# elrs_TX_E28.net
KiCad netlist of a schematic drawn in EasyEDA
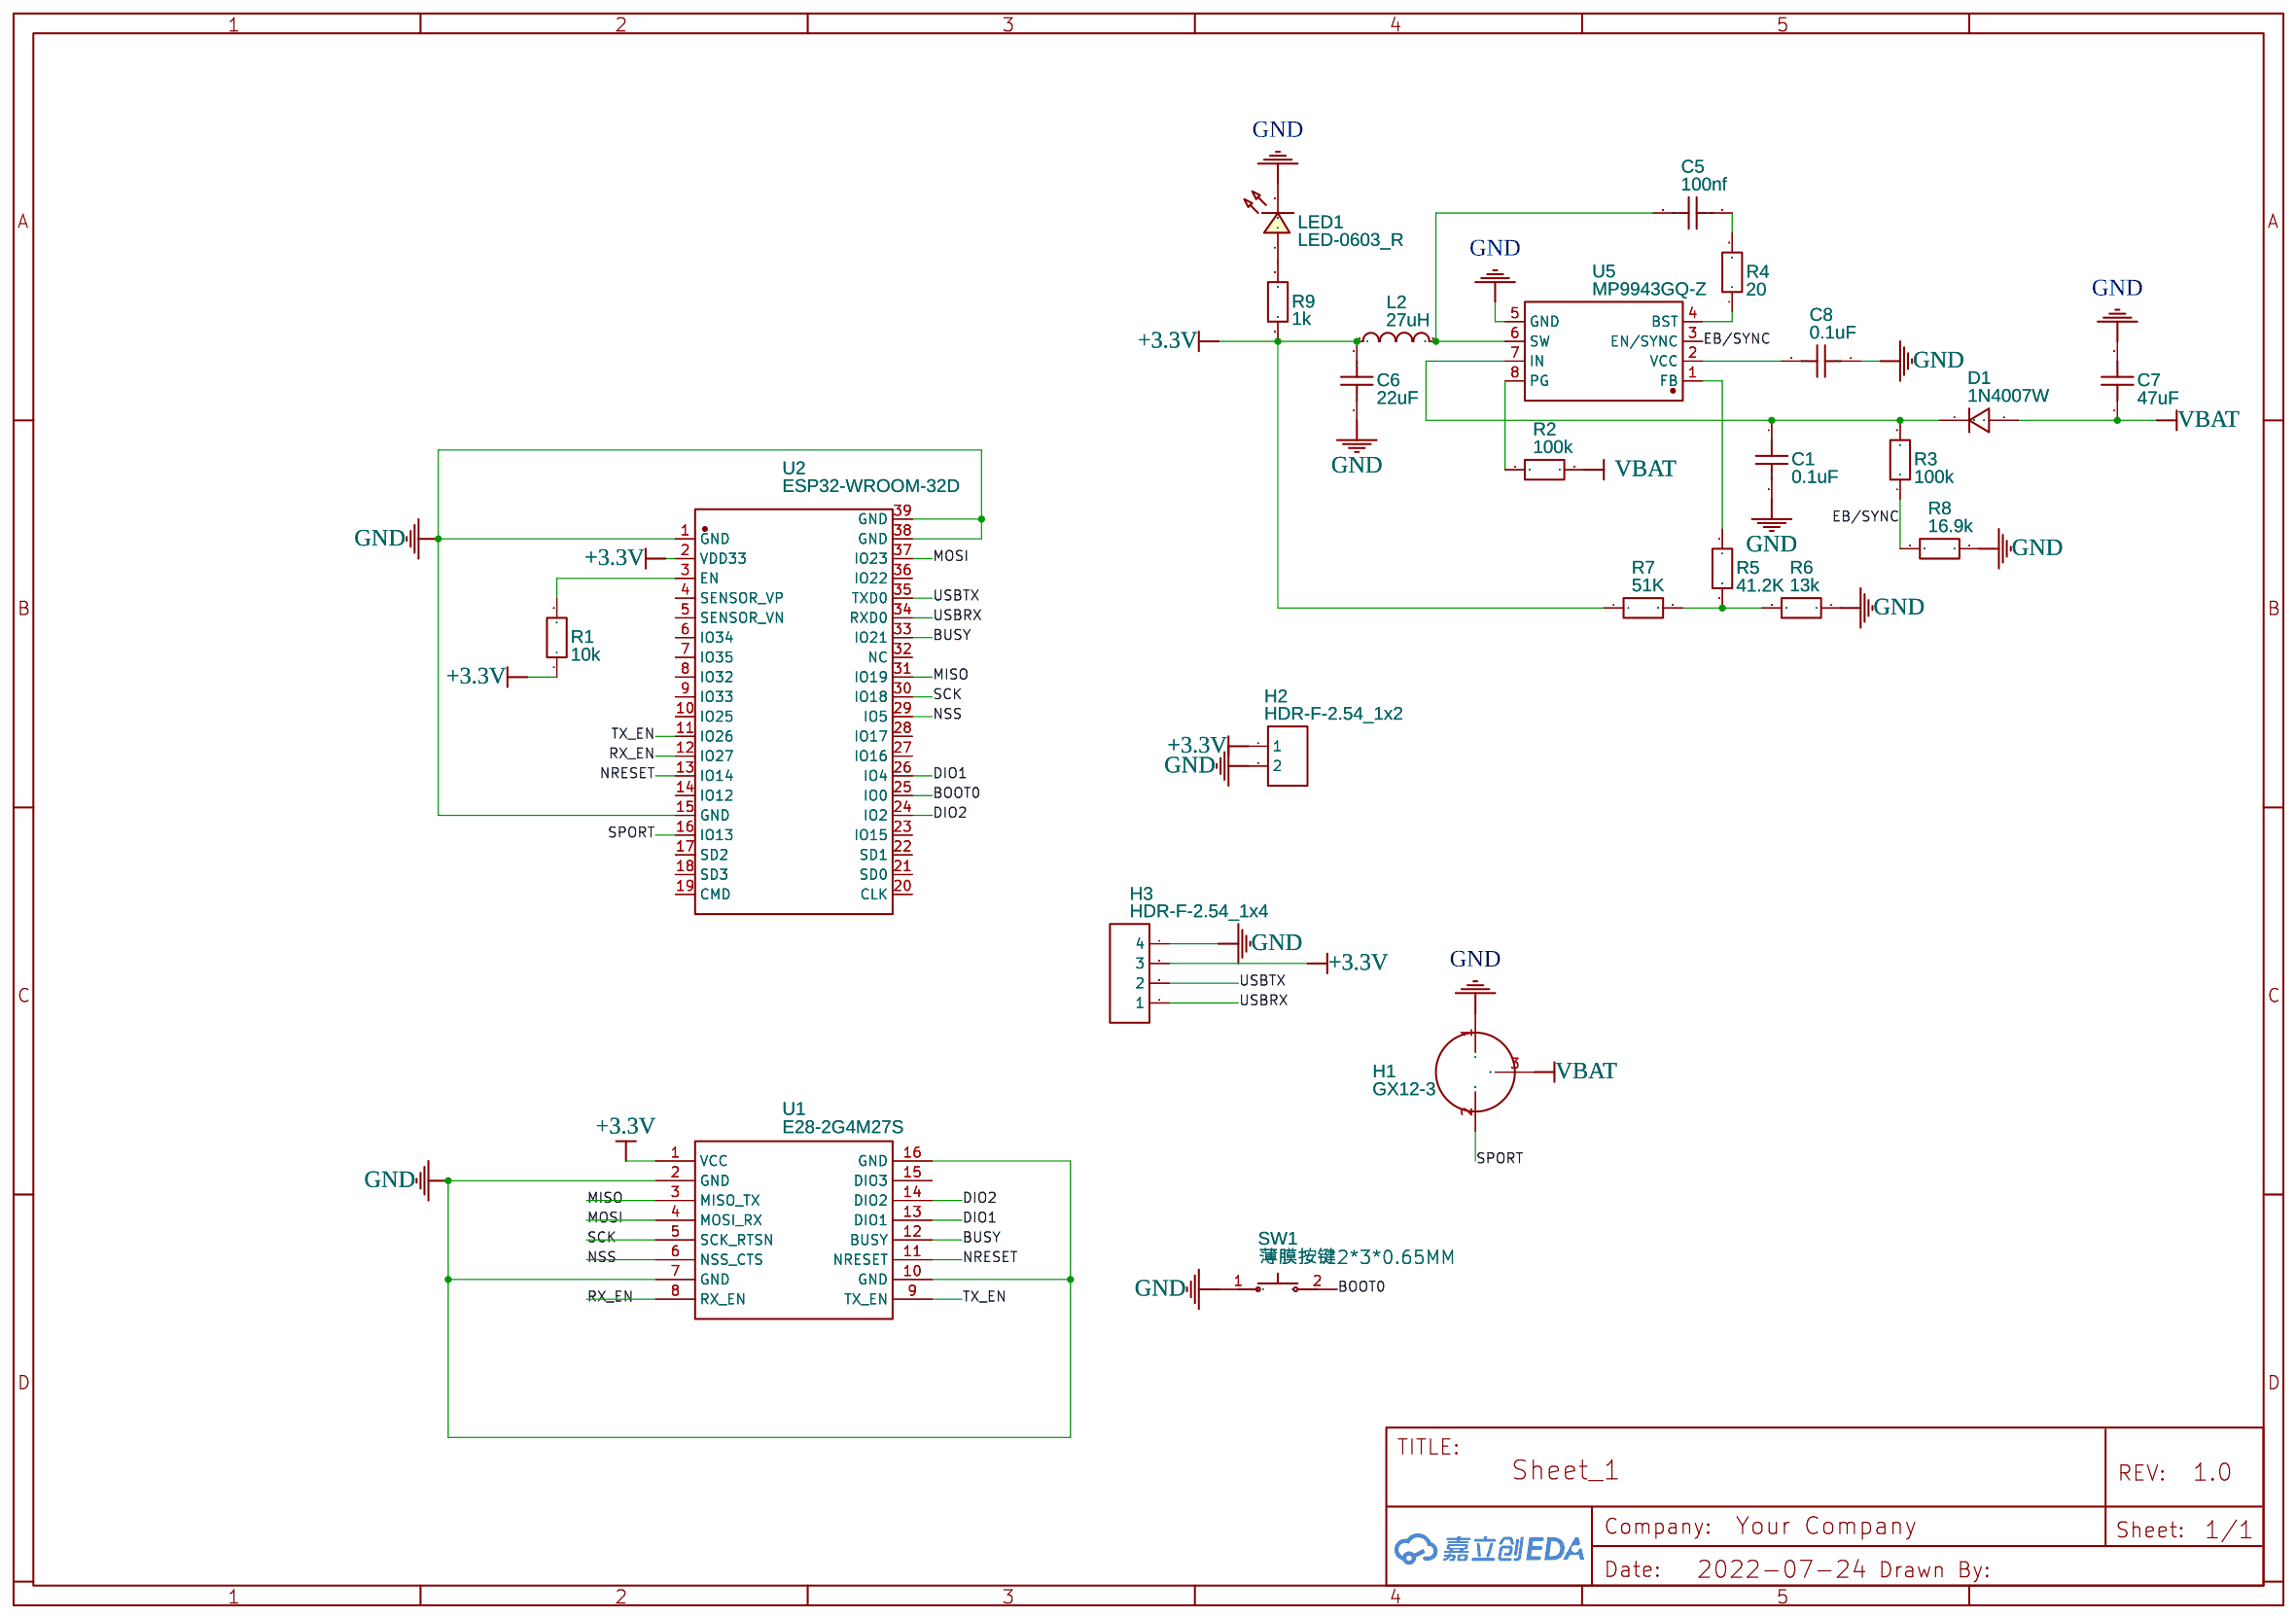
[diagram p0: schematic sheet]

(export (version "E")
  (design (tool "Eeschema 10.0.6"))
  (components
    (comp (ref "C1") (value "0.1uF") (libsource (lib "") (part "C_0603_US_1")))
    (comp (ref "C5") (value "100nf") (libsource (lib "") (part "C_0603_US")))
    (comp (ref "C6") (value "22uF") (libsource (lib "") (part "C_0603_US_2")))
    (comp (ref "C7") (value "47uF") (libsource (lib "") (part "C_0603_US_2")))
    (comp (ref "C8") (value "0.1uF") (libsource (lib "") (part "C_0603_US")))
    (comp (ref "D1")
      (value "1N4007W")
      (fields (field (name "BOM_Supplier Part") "C328592"))
      (libsource (lib "") (part "1N4007W"))
    )
    (comp (ref "H1") (value "GX12-3") (libsource (lib "") (part "GX12-3")))
    (comp (ref "H2")
      (value "HDR-F-2.54_1x2")
      (fields (field (name "BOM_Supplier Part") "C49661"))
      (libsource (lib "") (part "HDR-F-2.54_1x2"))
    )
    (comp (ref "H3")
      (value "HDR-F-2.54_1x4")
      (fields (field (name "BOM_Supplier Part") "C225501"))
      (libsource (lib "") (part "HDR-F-2.54_1x4"))
    )
    (comp (ref "L2") (value "27uH") (libsource (lib "") (part "L0603_US")))
    (comp (ref "LED1")
      (value "LED-0603_R")
      (fields
        (field (name "BOM_Manufacturer Part") "19-217/R6C-AL1M2VY/3T")
        (field (name "BOM_Supplier Part") "C72044")
      )
      (libsource (lib "") (part "LED-0603_R"))
    )
    (comp (ref "R1") (value "10k") (libsource (lib "") (part "R_0603_EU_2")))
    (comp (ref "R2") (value "100k") (libsource (lib "") (part "R_0603_EU")))
    (comp (ref "R3") (value "100k") (libsource (lib "") (part "R_0603_EU_2")))
    (comp (ref "R4") (value "20") (libsource (lib "") (part "R_0603_EU_2")))
    (comp (ref "R5") (value "41.2K") (libsource (lib "") (part "R_0603_EU_1")))
    (comp (ref "R6") (value "13k") (libsource (lib "") (part "R_0603_EU_3")))
    (comp (ref "R7") (value "51K") (libsource (lib "") (part "R_0603_EU")))
    (comp (ref "R8") (value "16.9k") (libsource (lib "") (part "R_0603_EU_3")))
    (comp (ref "R9") (value "1k") (libsource (lib "") (part "R_0603_EU_2")))
    (comp (ref "SW1")
      (value "薄膜按键2*3*0.65MM")
      (fields (field (name "BOM_Supplier Part") "C9900015708"))
      (libsource (lib "") (part "薄膜按键2*3*0.65MM"))
    )
    (comp (ref "U1")
      (value "E28-2G4M27S")
      (fields (field (name "BOM_Supplier Part") "C411312"))
      (libsource (lib "") (part "E28-2G4M27S"))
    )
    (comp (ref "U2")
      (value "ESP32-WROOM-32D")
      (fields (field (name "BOM_Supplier Part") "C473012"))
      (libsource (lib "") (part "ESP32-WROOM-32D"))
    )
    (comp (ref "U5")
      (value "MP9943GQ-Z")
      (fields (field (name "BOM_Supplier Part") "C477821"))
      (libsource (lib "") (part "MP9943GQ-Z"))
    )
  )
  (nets
    (net (code "1") (name "+3.3V") (class "Default")
      (node (ref "C6") (pin "2") (pinfunction "2_2") (pintype "unspecified"))
      (node (ref "H2") (pin "1") (pinfunction "1_1") (pintype "input"))
      (node (ref "H3") (pin "3") (pinfunction "3_3") (pintype "unspecified"))
      (node (ref "L2") (pin "1") (pinfunction "1_1") (pintype "unspecified"))
      (node (ref "R1") (pin "1") (pinfunction "1_1") (pintype "unspecified"))
      (node (ref "R7") (pin "1") (pinfunction "1_1") (pintype "unspecified"))
      (node (ref "R9") (pin "1") (pinfunction "1_1") (pintype "unspecified"))
      (node (ref "U1") (pin "1") (pinfunction "VCC_1") (pintype "unspecified"))
      (node (ref "U2") (pin "2") (pinfunction "VDD33_2") (pintype "unspecified"))
    )
    (net (code "2") (name "/BOOT0") (class "Default")
      (node (ref "SW1") (pin "2") (pinfunction "2_2") (pintype "unspecified"))
      (node (ref "U2") (pin "25") (pinfunction "IO0_25") (pintype "unspecified"))
    )
    (net (code "3") (name "/BUSY") (class "Default")
      (node (ref "U1") (pin "12") (pinfunction "BUSY_12") (pintype "unspecified"))
      (node (ref "U2") (pin "33") (pinfunction "IO21_33") (pintype "unspecified"))
    )
    (net (code "4") (name "/DIO1") (class "Default")
      (node (ref "U1") (pin "13") (pinfunction "DIO1_13") (pintype "unspecified"))
      (node (ref "U2") (pin "26") (pinfunction "IO4_26") (pintype "unspecified"))
    )
    (net (code "5") (name "/DIO2") (class "Default")
      (node (ref "U1") (pin "14") (pinfunction "DIO2_14") (pintype "unspecified"))
      (node (ref "U2") (pin "24") (pinfunction "IO2_24") (pintype "unspecified"))
    )
    (net (code "6") (name "/EB{slash}SYNC") (class "Default")
      (node (ref "R3") (pin "1") (pinfunction "1_1") (pintype "unspecified"))
      (node (ref "R8") (pin "2") (pinfunction "2_2") (pintype "unspecified"))
      (node (ref "U5") (pin "3") (pinfunction "EN/SYNC_3") (pintype "unspecified"))
    )
    (net (code "7") (name "/MISO") (class "Default")
      (node (ref "U1") (pin "3") (pinfunction "MISO_TX_3") (pintype "unspecified"))
      (node (ref "U2") (pin "31") (pinfunction "IO19_31") (pintype "unspecified"))
    )
    (net (code "8") (name "/MOSI") (class "Default")
      (node (ref "U1") (pin "4") (pinfunction "MOSI_RX_4") (pintype "unspecified"))
      (node (ref "U2") (pin "37") (pinfunction "IO23_37") (pintype "unspecified"))
    )
    (net (code "9") (name "/NRESET") (class "Default")
      (node (ref "U1") (pin "11") (pinfunction "NRESET_11") (pintype "unspecified"))
      (node (ref "U2") (pin "13") (pinfunction "IO14_13") (pintype "unspecified"))
    )
    (net (code "10") (name "/NSS") (class "Default")
      (node (ref "U1") (pin "6") (pinfunction "NSS_CTS_6") (pintype "unspecified"))
      (node (ref "U2") (pin "29") (pinfunction "IO5_29") (pintype "unspecified"))
    )
    (net (code "11") (name "/RX_EN") (class "Default")
      (node (ref "U1") (pin "8") (pinfunction "RX_EN_8") (pintype "unspecified"))
      (node (ref "U2") (pin "12") (pinfunction "IO27_12") (pintype "unspecified"))
    )
    (net (code "12") (name "/SCK") (class "Default")
      (node (ref "U1") (pin "5") (pinfunction "SCK_RTSN_5") (pintype "unspecified"))
      (node (ref "U2") (pin "30") (pinfunction "IO18_30") (pintype "unspecified"))
    )
    (net (code "13") (name "/SPORT") (class "Default")
      (node (ref "H1") (pin "2") (pinfunction "2_2") (pintype "unspecified"))
      (node (ref "U2") (pin "16") (pinfunction "IO13_16") (pintype "unspecified"))
    )
    (net (code "14") (name "/TX_EN") (class "Default")
      (node (ref "U1") (pin "9") (pinfunction "TX_EN_9") (pintype "unspecified"))
      (node (ref "U2") (pin "11") (pinfunction "IO26_11") (pintype "unspecified"))
    )
    (net (code "15") (name "/USBRX") (class "Default")
      (node (ref "H3") (pin "1") (pinfunction "1_1") (pintype "unspecified"))
      (node (ref "U2") (pin "34") (pinfunction "RXD0_34") (pintype "unspecified"))
    )
    (net (code "16") (name "/USBTX") (class "Default")
      (node (ref "H3") (pin "2") (pinfunction "2_2") (pintype "unspecified"))
      (node (ref "U2") (pin "35") (pinfunction "TXD0_35") (pintype "unspecified"))
    )
    (net (code "17") (name "GND") (class "Default")
      (node (ref "C1") (pin "2") (pinfunction "2_2") (pintype "unspecified"))
      (node (ref "C6") (pin "1") (pinfunction "1_1") (pintype "unspecified"))
      (node (ref "C7") (pin "2") (pinfunction "2_2") (pintype "unspecified"))
      (node (ref "C8") (pin "1") (pinfunction "1_1") (pintype "unspecified"))
      (node (ref "H1") (pin "1") (pinfunction "1_1") (pintype "unspecified"))
      (node (ref "H2") (pin "2") (pinfunction "2_2") (pintype "input"))
      (node (ref "H3") (pin "4") (pinfunction "4_4") (pintype "unspecified"))
      (node (ref "LED1") (pin "2") (pinfunction "2_2") (pintype "unspecified"))
      (node (ref "R6") (pin "1") (pinfunction "1_1") (pintype "unspecified"))
      (node (ref "R8") (pin "1") (pinfunction "1_1") (pintype "unspecified"))
      (node (ref "SW1") (pin "1") (pinfunction "1_1") (pintype "unspecified"))
      (node (ref "U1") (pin "10") (pinfunction "GND_10") (pintype "unspecified"))
      (node (ref "U1") (pin "16") (pinfunction "GND_16") (pintype "unspecified"))
      (node (ref "U1") (pin "2") (pinfunction "GND_2") (pintype "unspecified"))
      (node (ref "U1") (pin "7") (pinfunction "GND_7") (pintype "unspecified"))
      (node (ref "U2") (pin "1") (pinfunction "GND_1") (pintype "unspecified"))
      (node (ref "U2") (pin "15") (pinfunction "GND_15") (pintype "unspecified"))
      (node (ref "U2") (pin "38") (pinfunction "GND_38") (pintype "unspecified"))
      (node (ref "U2") (pin "39") (pinfunction "GND_39") (pintype "unspecified"))
      (node (ref "U5") (pin "5") (pinfunction "GND_5") (pintype "unspecified"))
    )
    (net (code "18") (name "Net-(C5-Pad1)") (class "Default")
      (node (ref "C5") (pin "1") (pinfunction "1_1") (pintype "unspecified"))
      (node (ref "R4") (pin "2") (pinfunction "2_2") (pintype "unspecified"))
    )
    (net (code "19") (name "Net-(LED1-Pad1)") (class "Default")
      (node (ref "LED1") (pin "1") (pinfunction "1_1") (pintype "unspecified"))
      (node (ref "R9") (pin "2") (pinfunction "2_2") (pintype "unspecified"))
    )
    (net (code "20") (name "Net-(R5-Pad2)") (class "Default")
      (node (ref "R5") (pin "2") (pinfunction "2_2") (pintype "unspecified"))
      (node (ref "R6") (pin "2") (pinfunction "2_2") (pintype "unspecified"))
      (node (ref "R7") (pin "2") (pinfunction "2_2") (pintype "unspecified"))
    )
    (net (code "21") (name "Net-(U2-EN)") (class "Default")
      (node (ref "R1") (pin "2") (pinfunction "2_2") (pintype "unspecified"))
      (node (ref "U2") (pin "3") (pinfunction "EN_3") (pintype "unspecified"))
    )
    (net (code "22") (name "Net-(U5-BST)") (class "Default")
      (node (ref "R4") (pin "1") (pinfunction "1_1") (pintype "unspecified"))
      (node (ref "U5") (pin "4") (pinfunction "BST_4") (pintype "unspecified"))
    )
    (net (code "23") (name "Net-(U5-FB)") (class "Default")
      (node (ref "R5") (pin "1") (pinfunction "1_1") (pintype "unspecified"))
      (node (ref "U5") (pin "1") (pinfunction "FB_1") (pintype "unspecified"))
    )
    (net (code "24") (name "Net-(U5-IN)") (class "Default")
      (node (ref "C1") (pin "1") (pinfunction "1_1") (pintype "unspecified"))
      (node (ref "D1") (pin "1") (pinfunction "1_1") (pintype "unspecified"))
      (node (ref "R3") (pin "2") (pinfunction "2_2") (pintype "unspecified"))
      (node (ref "U5") (pin "7") (pinfunction "IN_7") (pintype "unspecified"))
    )
    (net (code "25") (name "Net-(U5-PG)") (class "Default")
      (node (ref "R2") (pin "1") (pinfunction "1_1") (pintype "unspecified"))
      (node (ref "U5") (pin "8") (pinfunction "PG_8") (pintype "unspecified"))
    )
    (net (code "26") (name "Net-(U5-SW)") (class "Default")
      (node (ref "C5") (pin "2") (pinfunction "2_2") (pintype "unspecified"))
      (node (ref "L2") (pin "2") (pinfunction "2_2") (pintype "unspecified"))
      (node (ref "U5") (pin "6") (pinfunction "SW_6") (pintype "unspecified"))
    )
    (net (code "27") (name "Net-(U5-VCC)") (class "Default")
      (node (ref "C8") (pin "2") (pinfunction "2_2") (pintype "unspecified"))
      (node (ref "U5") (pin "2") (pinfunction "VCC_2") (pintype "unspecified"))
    )
    (net (code "28") (name "VBAT") (class "Default")
      (node (ref "C7") (pin "1") (pinfunction "1_1") (pintype "unspecified"))
      (node (ref "D1") (pin "2") (pinfunction "2_2") (pintype "unspecified"))
      (node (ref "H1") (pin "3") (pinfunction "3_3") (pintype "unspecified"))
      (node (ref "R2") (pin "2") (pinfunction "2_2") (pintype "unspecified"))
    )
    (net (code "29") (name "unconnected-(U1-DIO3-Pad15)") (class "Default")
      (node (ref "U1") (pin "15") (pinfunction "DIO3_15") (pintype "unspecified"))
    )
    (net (code "30") (name "unconnected-(U2-CLK-Pad20)") (class "Default")
      (node (ref "U2") (pin "20") (pinfunction "CLK_20") (pintype "unspecified"))
    )
    (net (code "31") (name "unconnected-(U2-CMD-Pad19)") (class "Default")
      (node (ref "U2") (pin "19") (pinfunction "CMD_19") (pintype "unspecified"))
    )
    (net (code "32") (name "unconnected-(U2-IO12-Pad14)") (class "Default")
      (node (ref "U2") (pin "14") (pinfunction "IO12_14") (pintype "unspecified"))
    )
    (net (code "33") (name "unconnected-(U2-IO15-Pad23)") (class "Default")
      (node (ref "U2") (pin "23") (pinfunction "IO15_23") (pintype "unspecified"))
    )
    (net (code "34") (name "unconnected-(U2-IO16-Pad27)") (class "Default")
      (node (ref "U2") (pin "27") (pinfunction "IO16_27") (pintype "unspecified"))
    )
    (net (code "35") (name "unconnected-(U2-IO17-Pad28)") (class "Default")
      (node (ref "U2") (pin "28") (pinfunction "IO17_28") (pintype "unspecified"))
    )
    (net (code "36") (name "unconnected-(U2-IO22-Pad36)") (class "Default")
      (node (ref "U2") (pin "36") (pinfunction "IO22_36") (pintype "unspecified"))
    )
    (net (code "37") (name "unconnected-(U2-IO25-Pad10)") (class "Default")
      (node (ref "U2") (pin "10") (pinfunction "IO25_10") (pintype "unspecified"))
    )
    (net (code "38") (name "unconnected-(U2-IO32-Pad8)") (class "Default")
      (node (ref "U2") (pin "8") (pinfunction "IO32_8") (pintype "unspecified"))
    )
    (net (code "39") (name "unconnected-(U2-IO33-Pad9)") (class "Default")
      (node (ref "U2") (pin "9") (pinfunction "IO33_9") (pintype "unspecified"))
    )
    (net (code "40") (name "unconnected-(U2-IO34-Pad6)") (class "Default")
      (node (ref "U2") (pin "6") (pinfunction "IO34_6") (pintype "unspecified"))
    )
    (net (code "41") (name "unconnected-(U2-IO35-Pad7)") (class "Default")
      (node (ref "U2") (pin "7") (pinfunction "IO35_7") (pintype "unspecified"))
    )
    (net (code "42") (name "unconnected-(U2-NC-Pad32)") (class "Default")
      (node (ref "U2") (pin "32") (pinfunction "NC_32") (pintype "unspecified"))
    )
    (net (code "43") (name "unconnected-(U2-SD0-Pad21)") (class "Default")
      (node (ref "U2") (pin "21") (pinfunction "SD0_21") (pintype "unspecified"))
    )
    (net (code "44") (name "unconnected-(U2-SD1-Pad22)") (class "Default")
      (node (ref "U2") (pin "22") (pinfunction "SD1_22") (pintype "unspecified"))
    )
    (net (code "45") (name "unconnected-(U2-SD2-Pad17)") (class "Default")
      (node (ref "U2") (pin "17") (pinfunction "SD2_17") (pintype "unspecified"))
    )
    (net (code "46") (name "unconnected-(U2-SD3-Pad18)") (class "Default")
      (node (ref "U2") (pin "18") (pinfunction "SD3_18") (pintype "unspecified"))
    )
    (net (code "47") (name "unconnected-(U2-SENSOR_VN-Pad5)") (class "Default")
      (node (ref "U2") (pin "5") (pinfunction "SENSOR_VN_5") (pintype "unspecified"))
    )
    (net (code "48") (name "unconnected-(U2-SENSOR_VP-Pad4)") (class "Default")
      (node (ref "U2") (pin "4") (pinfunction "SENSOR_VP_4") (pintype "unspecified"))
    )
  )
)
